# Keyboard.net
KiCad netlist of a schematic drawn in Altium Designer
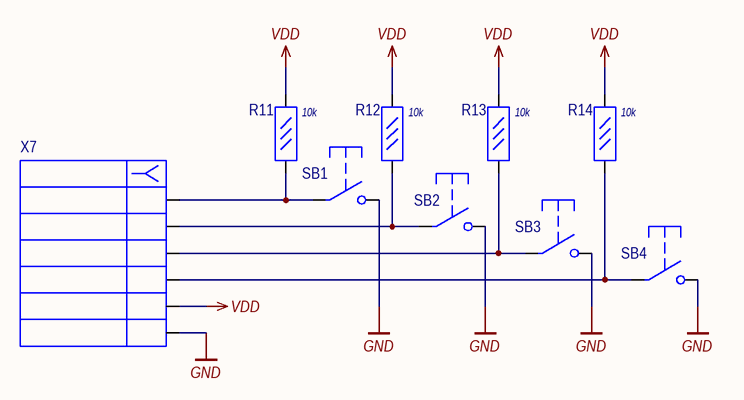
[diagram p0: Keyboard.SchDoc]

(export (version "E")
  (design (tool "Eeschema 10.0.6"))
  (components
    (comp (ref "R11")
      (value "Resistor (0.05W)")
      (footprint "Resistor SMD 1206")
      (fields (field (name "R") "10k"))
      (libsource (lib "Components") (part "Resistor (0.05W)"))
    )
    (comp (ref "R12")
      (value "Resistor (0.05W)")
      (footprint "Resistor SMD 1206")
      (fields (field (name "R") "10k"))
      (libsource (lib "Components") (part "Resistor (0.05W)"))
    )
    (comp (ref "R13")
      (value "Resistor (0.05W)")
      (footprint "Resistor SMD 1206")
      (fields (field (name "R") "10k"))
      (libsource (lib "Components") (part "Resistor (0.05W)"))
    )
    (comp (ref "R14")
      (value "Resistor (0.05W)")
      (footprint "Resistor SMD 1206")
      (fields (field (name "R") "10k"))
      (libsource (lib "Components") (part "Resistor (0.05W)"))
    )
    (comp (ref "SB1")
      (value "Button")
      (footprint "BUTTON SMD")
      (libsource (lib "Components") (part "Button"))
    )
    (comp (ref "SB2")
      (value "Button")
      (footprint "BUTTON SMD")
      (libsource (lib "Components") (part "Button"))
    )
    (comp (ref "SB3")
      (value "Button")
      (footprint "BUTTON SMD")
      (libsource (lib "Components") (part "Button"))
    )
    (comp (ref "SB4")
      (value "Button")
      (footprint "BUTTON SMD")
      (libsource (lib "Components") (part "Button"))
    )
    (comp (ref "X7")
      (value "KBD_Connector")
      (footprint "KBD_Connector")
      (libsource (lib "Components") (part "KBD_Connector"))
    )
  )
  (nets
    (net (code "1") (name "GND") (class "Default")
      (node (ref "SB1") (pin "2") (pintype "passive"))
      (node (ref "SB2") (pin "2") (pintype "passive"))
      (node (ref "SB3") (pin "2") (pintype "passive"))
      (node (ref "SB4") (pin "2") (pintype "passive"))
      (node (ref "X7") (pin "6") (pintype "passive"))
    )
    (net (code "2") (name "Net-(R11-Pad2)") (class "Default")
      (node (ref "R11") (pin "2") (pintype "passive"))
      (node (ref "SB1") (pin "1") (pintype "passive"))
      (node (ref "X7") (pin "1") (pintype "passive"))
    )
    (net (code "3") (name "Net-(R12-Pad2)") (class "Default")
      (node (ref "R12") (pin "2") (pintype "passive"))
      (node (ref "SB2") (pin "1") (pintype "passive"))
      (node (ref "X7") (pin "2") (pintype "passive"))
    )
    (net (code "4") (name "Net-(R13-Pad2)") (class "Default")
      (node (ref "R13") (pin "2") (pintype "passive"))
      (node (ref "SB3") (pin "1") (pintype "passive"))
      (node (ref "X7") (pin "3") (pintype "passive"))
    )
    (net (code "5") (name "Net-(R14-Pad2)") (class "Default")
      (node (ref "R14") (pin "2") (pintype "passive"))
      (node (ref "SB4") (pin "1") (pintype "passive"))
      (node (ref "X7") (pin "4") (pintype "passive"))
    )
    (net (code "6") (name "VDD") (class "Default")
      (node (ref "R11") (pin "1") (pintype "passive"))
      (node (ref "R12") (pin "1") (pintype "passive"))
      (node (ref "R13") (pin "1") (pintype "passive"))
      (node (ref "R14") (pin "1") (pintype "passive"))
      (node (ref "X7") (pin "5") (pintype "passive"))
    )
  )
)
